# Controller_PCB.net
KiCad netlist of a schematic drawn in EasyEDA Pro
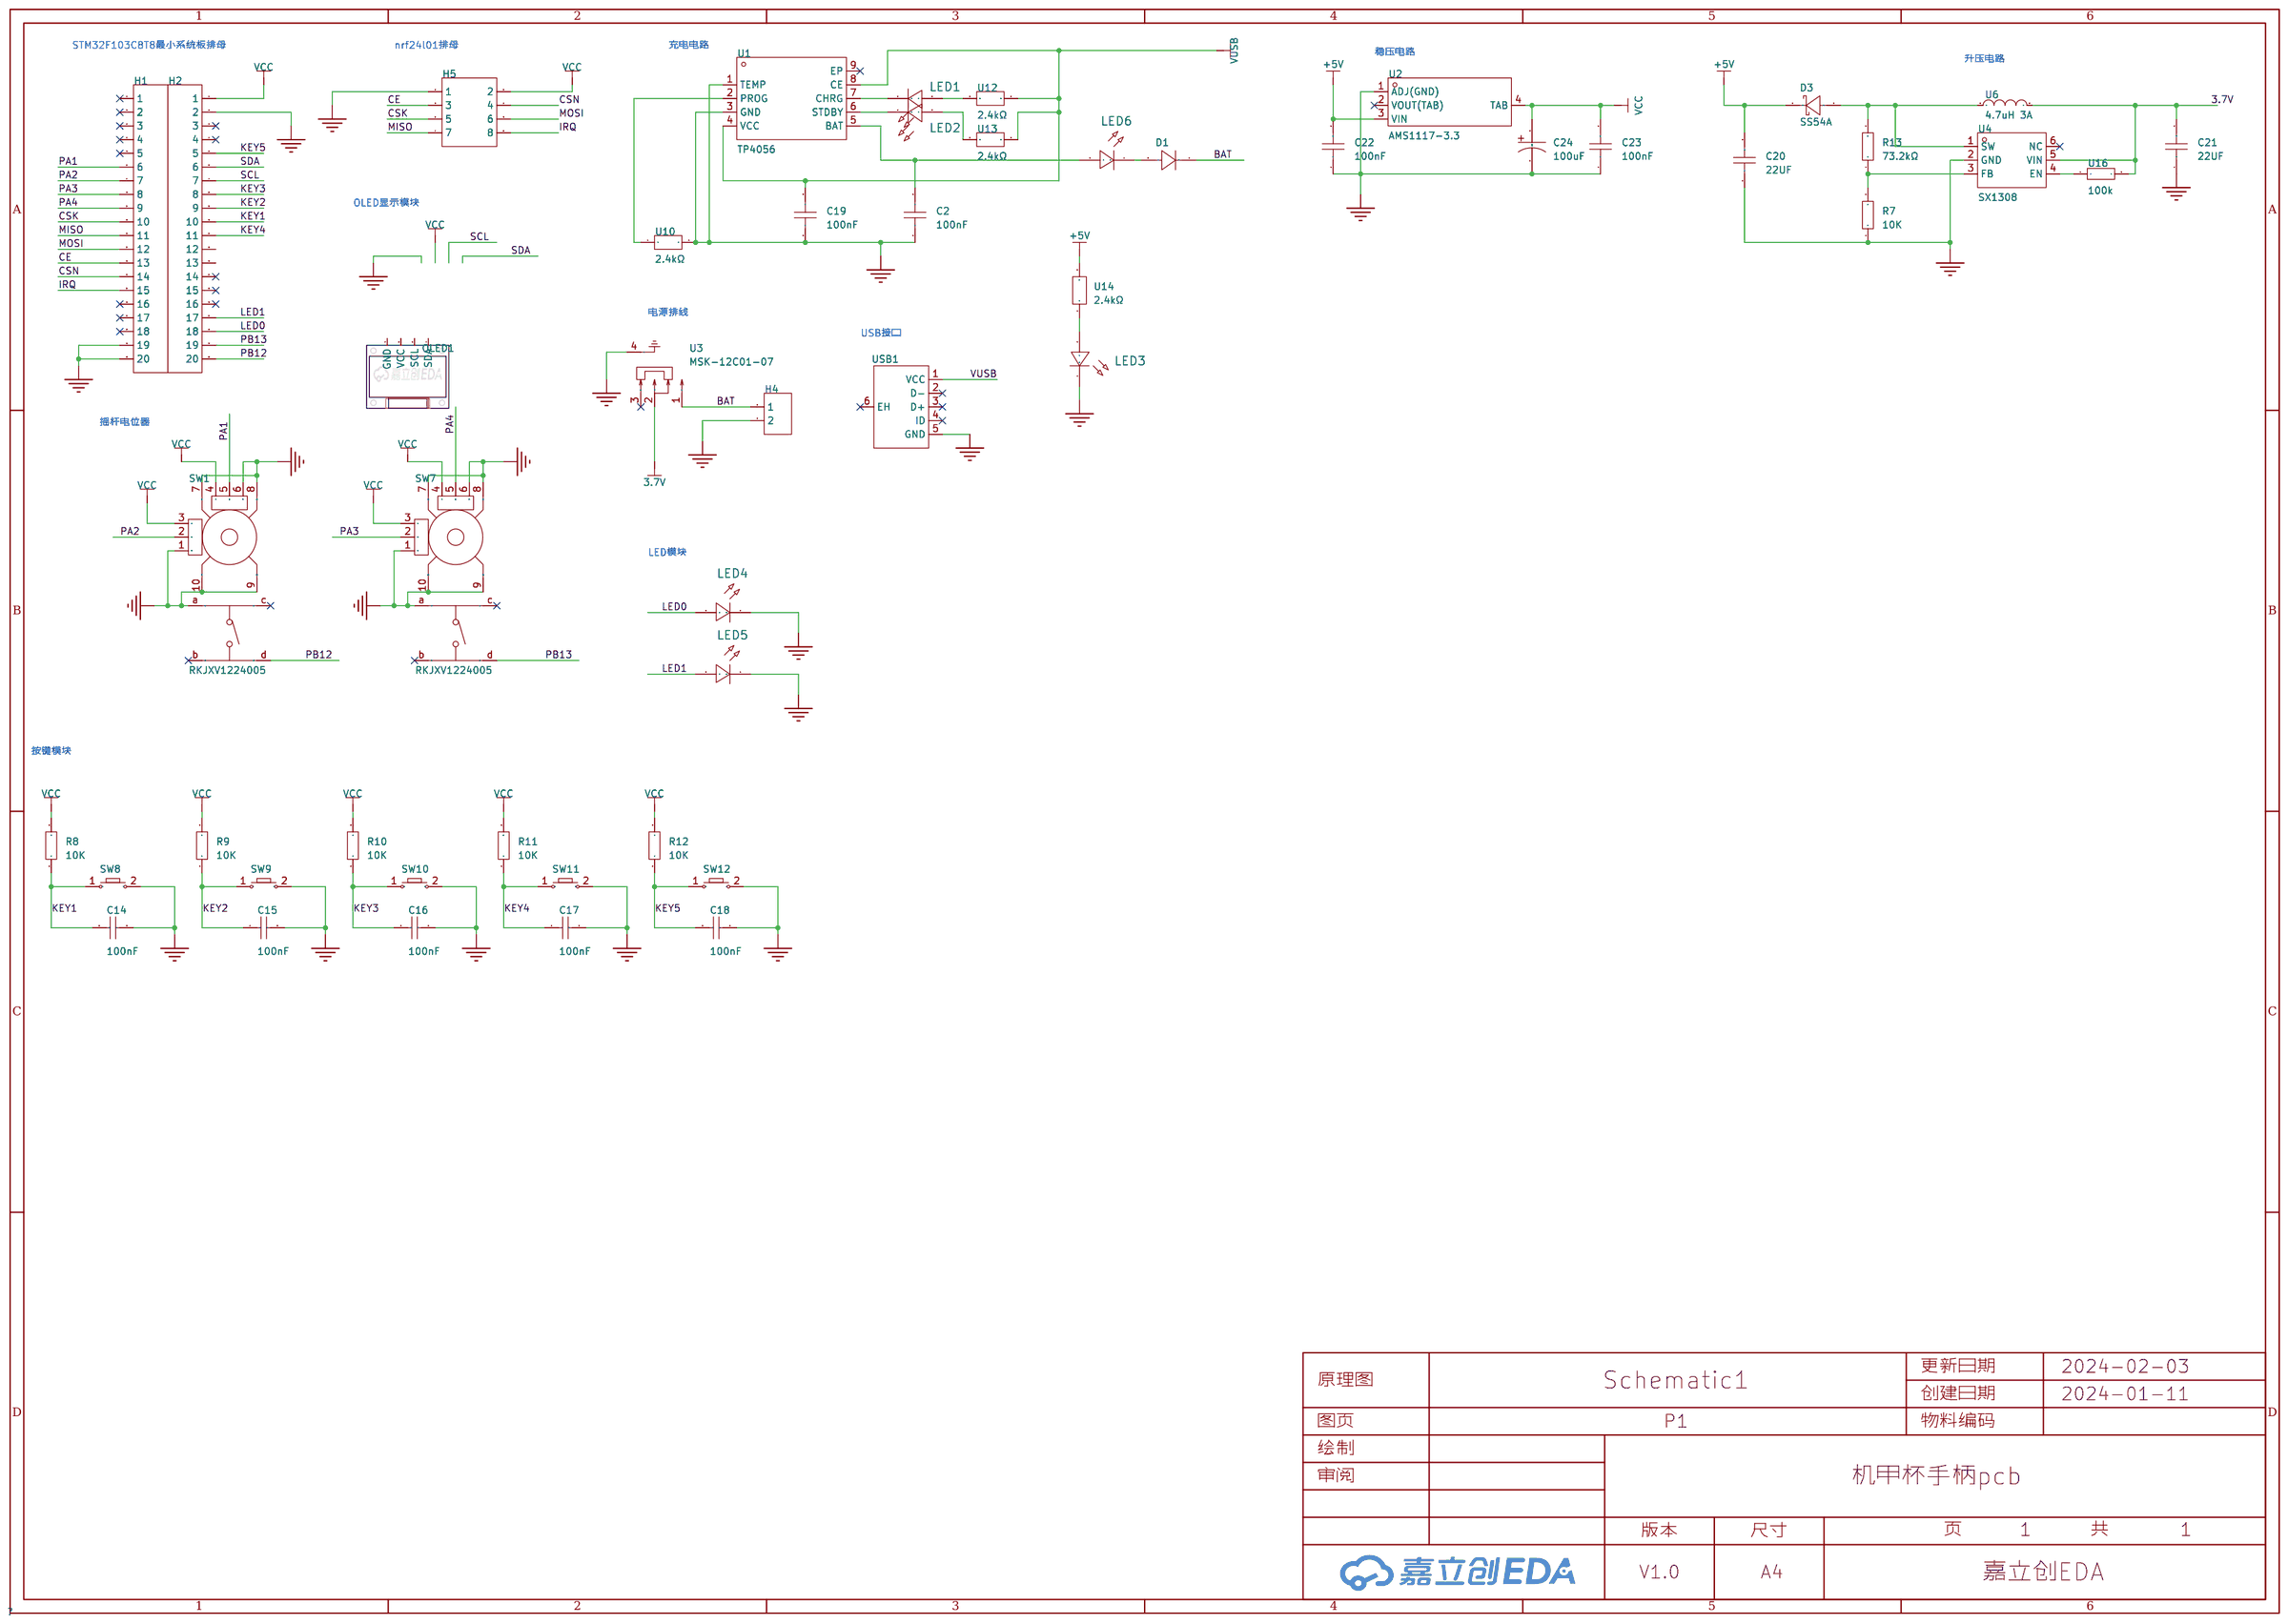
[diagram p0: schematic sheet]

(export (version "E")
  (design (tool "Eeschema 10.0.6"))
  (components
    (comp (ref "C2")
      (value "100nF")
      (footprint "easyedapro:C0805")
      (fields
        (field (name "Manufacturer Part") "CL21B104KCFNNNE")
        (field (name "Manufacturer") "SAMSUNG(三星)")
      )
      (libsource (lib "easyedapro") (part "CapAcitance"))
    )
    (comp (ref "C14")
      (value "100nF")
      (footprint "easyedapro:C0805")
      (description "容值:100nF;精度:±10%;额定电压:100V;材质(温度系数):X7R;")
      (fields
        (field (name "Manufacturer Part") "CL21B104KCFNNNE")
        (field (name "Manufacturer") "SAMSUNG(三星)")
      )
      (libsource (lib "easyedapro") (part "CL21B104KCFNNNE"))
    )
    (comp (ref "C15")
      (value "100nF")
      (footprint "easyedapro:C0805")
      (description "容值:100nF;精度:±10%;额定电压:100V;材质(温度系数):X7R;")
      (fields
        (field (name "Manufacturer Part") "CL21B104KCFNNNE")
        (field (name "Manufacturer") "SAMSUNG(三星)")
      )
      (libsource (lib "easyedapro") (part "CL21B104KCFNNNE"))
    )
    (comp (ref "C16")
      (value "100nF")
      (footprint "easyedapro:C0805")
      (description "容值:100nF;精度:±10%;额定电压:100V;材质(温度系数):X7R;")
      (fields
        (field (name "Manufacturer Part") "CL21B104KCFNNNE")
        (field (name "Manufacturer") "SAMSUNG(三星)")
      )
      (libsource (lib "easyedapro") (part "CL21B104KCFNNNE"))
    )
    (comp (ref "C17")
      (value "100nF")
      (footprint "easyedapro:C0805")
      (description "容值:100nF;精度:±10%;额定电压:100V;材质(温度系数):X7R;")
      (fields
        (field (name "Manufacturer Part") "CL21B104KCFNNNE")
        (field (name "Manufacturer") "SAMSUNG(三星)")
      )
      (libsource (lib "easyedapro") (part "CL21B104KCFNNNE"))
    )
    (comp (ref "C18")
      (value "100nF")
      (footprint "easyedapro:C0805")
      (description "容值:100nF;精度:±10%;额定电压:100V;材质(温度系数):X7R;")
      (fields
        (field (name "Manufacturer Part") "CL21B104KCFNNNE")
        (field (name "Manufacturer") "SAMSUNG(三星)")
      )
      (libsource (lib "easyedapro") (part "CL21B104KCFNNNE"))
    )
    (comp (ref "C19")
      (value "100nF")
      (footprint "easyedapro:C0805")
      (fields
        (field (name "Manufacturer Part") "CL21B104KCFNNNE")
        (field (name "Manufacturer") "SAMSUNG(三星)")
      )
      (libsource (lib "easyedapro") (part "CapAcitance"))
    )
    (comp (ref "C20")
      (value "22UF")
      (footprint "easyedapro:C1206")
      (libsource (lib "easyedapro") (part "22UF_C9900008064"))
    )
    (comp (ref "C21")
      (value "22UF")
      (footprint "easyedapro:C1206")
      (libsource (lib "easyedapro") (part "22UF_C9900008064"))
    )
    (comp (ref "C22")
      (value "100nF")
      (footprint "easyedapro:C0603")
      (description "容值:100nF;精度:±10%;额定电压:50V;材质(温度系数):X7R;")
      (fields
        (field (name "Manufacturer Part") "CC0603KRX7R9BB104")
        (field (name "Manufacturer") "YAGEO(国巨)")
      )
      (libsource (lib "easyedapro") (part "CC0603KRX7R9BB104"))
    )
    (comp (ref "C23")
      (value "100nF")
      (footprint "easyedapro:C0603")
      (description "容值:100nF;精度:±10%;额定电压:50V;材质(温度系数):X7R;")
      (fields
        (field (name "Manufacturer Part") "CC0603KRX7R9BB104")
        (field (name "Manufacturer") "YAGEO(国巨)")
      )
      (libsource (lib "easyedapro") (part "CC0603KRX7R9BB104"))
    )
    (comp (ref "C24")
      (value "100uF")
      (footprint "easyedapro:CASE-D_7343")
      (description "容值:100uF;精度:±20%;额定电压:6.3V;等效串联电阻:400mΩ@100kHz;")
      (fields (field (name "Manufacturer Part") "NOJD107M006RWJ") (field (name "Manufacturer") "Kyocera AVX"))
      (libsource (lib "easyedapro") (part "NOJD107M006RWJ"))
    )
    (comp (ref "D1")
      (value "~")
      (footprint "easyedapro:DO_1N4007")
      (libsource (lib "easyedapro") (part "D_1N4007"))
    )
    (comp (ref "D3")
      (value "SS54A")
      (footprint "easyedapro:SMA_L4.2-W2.6-LS5.1-RD")
      (description "二极管配置:独立式;正向压降(Vf):550mV@5A;直流反向耐压(Vr):40V;平均整流电流(Io):5A;")
      (fields (field (name "Manufacturer") "FUXINSEMI(富芯森美)"))
      (libsource (lib "easyedapro") (part "SS54A"))
    )
    (comp (ref "H1")
      (value "~")
      (footprint "easyedapro:HDR-TH_20P-P2.54-V-F")
      (libsource (lib "easyedapro") (part "HDR-F_2.54_1x20P"))
    )
    (comp (ref "H2")
      (value "~")
      (footprint "easyedapro:HDR-TH_20P-P2.54-V-F")
      (libsource (lib "easyedapro") (part "HDR-F_2.54_1x20P"))
    )
    (comp (ref "H4")
      (value "~")
      (footprint "easyedapro:HDR-TH_2P-P2.54-V-F")
      (libsource (lib "easyedapro") (part "Header-Female-2.54_1x2"))
    )
    (comp (ref "H5")
      (value "~")
      (footprint "easyedapro:HDR-TH_8P-P2.54-V-F-R2-C4-S2.54-1")
      (libsource (lib "easyedapro") (part "HDR-F-2.54_2x4"))
    )
    (comp (ref "LED1")
      (value "~")
      (footprint "easyedapro:LED_0603")
      (libsource (lib "easyedapro") (part "LED_R"))
    )
    (comp (ref "LED2")
      (value "~")
      (footprint "easyedapro:LED_0603")
      (libsource (lib "easyedapro") (part "LED_R"))
    )
    (comp (ref "LED3")
      (value "~")
      (footprint "easyedapro:LED_0603")
      (libsource (lib "easyedapro") (part "LED_R"))
    )
    (comp (ref "LED4")
      (value "~")
      (footprint "easyedapro:LED_0603")
      (libsource (lib "easyedapro") (part "LED_R"))
    )
    (comp (ref "LED5")
      (value "~")
      (footprint "easyedapro:LED_0603")
      (libsource (lib "easyedapro") (part "LED_R"))
    )
    (comp (ref "LED6")
      (value "~")
      (footprint "easyedapro:LED_0603")
      (libsource (lib "easyedapro") (part "LED_R"))
    )
    (comp (ref "OLED1")
      (value "~")
      (footprint "easyedapro:0.96OLED_4P")
      (libsource (lib "easyedapro") (part "0.96OLED模块_4P"))
    )
    (comp (ref "R7") (value "10K") (footprint "easyedapro:R1206") (libsource (lib "easyedapro") (part "电阻")))
    (comp (ref "R8") (value "10K") (footprint "easyedapro:R1206") (libsource (lib "easyedapro") (part "电阻")))
    (comp (ref "R9") (value "10K") (footprint "easyedapro:R1206") (libsource (lib "easyedapro") (part "电阻")))
    (comp (ref "R10") (value "10K") (footprint "easyedapro:R1206") (libsource (lib "easyedapro") (part "电阻")))
    (comp (ref "R11") (value "10K") (footprint "easyedapro:R1206") (libsource (lib "easyedapro") (part "电阻")))
    (comp (ref "R12") (value "10K") (footprint "easyedapro:R1206") (libsource (lib "easyedapro") (part "电阻")))
    (comp (ref "R13")
      (value "73.2kΩ")
      (footprint "easyedapro:R0603")
      (description "电阻类型:厚膜电阻;阻值:73.2kΩ;精度:±1%;功率:100mW;最大工作电压:75V;温度系数:±100ppm/°C;")
      (fields (field (name "Manufacturer Part") "AC0603FR-0773K2L") (field (name "Manufacturer") "YAGEO(国巨)"))
      (libsource (lib "easyedapro") (part "AC0603FR-0773K2L"))
    )
    (comp (ref "SW1")
      (value "RKJXV1224005")
      (footprint "easyedapro:SW-TH_RKJXV1224005")
      (description "操纵杆复位 中央按动开关 适用于航模玩具遥控器电位器、3D摇杆PS4手柄游戏机、无人机摇杆电位器、工业控制器")
      (fields (field (name "Manufacturer") "ALPSALPINE(阿尔卑斯阿尔派)"))
      (libsource (lib "easyedapro") (part "RKJXV1224005"))
    )
    (comp (ref "SW7")
      (value "RKJXV1224005")
      (footprint "easyedapro:SW-TH_RKJXV1224005")
      (description "操纵杆复位 中央按动开关 适用于航模玩具遥控器电位器、3D摇杆PS4手柄游戏机、无人机摇杆电位器、工业控制器")
      (fields (field (name "Manufacturer") "ALPSALPINE(阿尔卑斯阿尔派)"))
      (libsource (lib "easyedapro") (part "RKJXV1224005"))
    )
    (comp (ref "SW8")
      (value "~")
      (footprint "easyedapro:Key_SMD_3x4x2")
      (libsource (lib "easyedapro") (part "轻触按键x2"))
    )
    (comp (ref "SW9")
      (value "~")
      (footprint "easyedapro:Key_SMD_3x4x2")
      (libsource (lib "easyedapro") (part "轻触按键x2"))
    )
    (comp (ref "SW10")
      (value "~")
      (footprint "easyedapro:Key_SMD_3x4x2")
      (libsource (lib "easyedapro") (part "轻触按键x2"))
    )
    (comp (ref "SW11")
      (value "~")
      (footprint "easyedapro:Key_SMD_3x4x2")
      (libsource (lib "easyedapro") (part "轻触按键x2"))
    )
    (comp (ref "SW12")
      (value "~")
      (footprint "easyedapro:Key_SMD_3x4x2")
      (libsource (lib "easyedapro") (part "轻触按键x2"))
    )
    (comp (ref "U1")
      (value "TP4056")
      (footprint "easyedapro:ESOP-8_L4.9-W3.9-P1.27-LS6.0-BL-EP")
      (libsource (lib "easyedapro") (part "TP4056_C9900002169"))
    )
    (comp (ref "U2")
      (value "AMS1117-3.3")
      (footprint "easyedapro:SOT-223-4_L6.5-W3.5-P2.30-LS7.0-BR")
      (description "输出类型:固定;最大输入电压:18V;输出电压:3.3V;输出电流:1A;电源纹波抑制比(PSRR):60dB@(120Hz);输出极性:正;")
      (fields (field (name "Manufacturer") "UMW(友台半导体)"))
      (libsource (lib "easyedapro") (part "AMS1117-3.3_C347222"))
    )
    (comp (ref "U3")
      (value "MSK-12C01-07")
      (footprint "easyedapro:SW-SMD_MSK12CO2-BDM")
      (libsource (lib "easyedapro") (part "MSK-12C01-07"))
    )
    (comp (ref "U4")
      (value "SX1308")
      (footprint "easyedapro:SOT-23-6_L2.9-W1.6-P0.95-LS2.8-BL")
      (description "功能类型:升压型;同步整流:否;输出通道数:1;拓扑结构:升压式;输入电压:2V~24V;输出电压:28V;输出电流(最大值):-;开关频率:1.2MHz;")
      (fields (field (name "Manufacturer") "SX(硕芯科技)"))
      (libsource (lib "easyedapro") (part "SX1308"))
    )
    (comp (ref "U6")
      (value "4.7uH 3A")
      (footprint "easyedapro:IND-SMD_L7.3-W7.3_GSDRH74P")
      (libsource (lib "easyedapro") (part "4.7UH 3A"))
    )
    (comp (ref "U10")
      (value "2.4kΩ")
      (footprint "easyedapro:R0603")
      (description "电阻类型:薄膜电阻;阻值:2.4kΩ;精度:±0.1%;功率:100mW;最大工作电压:100V;温度系数:±10ppm/°C;")
      (fields (field (name "Manufacturer Part") "PTFR0603B2K40N9") (field (name "Manufacturer") "RESI(开步睿思）"))
      (libsource (lib "easyedapro") (part "PTFR0603B2K40N9"))
    )
    (comp (ref "U12")
      (value "2.4kΩ")
      (footprint "easyedapro:R0603")
      (description "电阻类型:薄膜电阻;阻值:2.4kΩ;精度:±0.1%;功率:100mW;最大工作电压:100V;温度系数:±10ppm/°C;")
      (fields (field (name "Manufacturer Part") "PTFR0603B2K40N9") (field (name "Manufacturer") "RESI(开步睿思）"))
      (libsource (lib "easyedapro") (part "PTFR0603B2K40N9"))
    )
    (comp (ref "U13")
      (value "2.4kΩ")
      (footprint "easyedapro:R0603")
      (description "电阻类型:薄膜电阻;阻值:2.4kΩ;精度:±0.1%;功率:100mW;最大工作电压:100V;温度系数:±10ppm/°C;")
      (fields (field (name "Manufacturer Part") "PTFR0603B2K40N9") (field (name "Manufacturer") "RESI(开步睿思）"))
      (libsource (lib "easyedapro") (part "PTFR0603B2K40N9"))
    )
    (comp (ref "U14")
      (value "2.4kΩ")
      (footprint "easyedapro:R0603")
      (description "电阻类型:薄膜电阻;阻值:2.4kΩ;精度:±0.1%;功率:100mW;最大工作电压:100V;温度系数:±10ppm/°C;")
      (fields (field (name "Manufacturer Part") "PTFR0603B2K40N9") (field (name "Manufacturer") "RESI(开步睿思）"))
      (libsource (lib "easyedapro") (part "PTFR0603B2K40N9"))
    )
    (comp (ref "U16")
      (value "100k")
      (footprint "easyedapro:R0603")
      (libsource (lib "easyedapro") (part "100K"))
    )
    (comp (ref "USB1")
      (value "~")
      (footprint "easyedapro:USB_Micro")
      (libsource (lib "easyedapro") (part "USB_Micro"))
    )
  )
  (nets
    (net (code "1") (name "+5V") (class "Default")
      (node (ref "C20") (pin "2") (pinfunction "2_2") (pintype "input"))
      (node (ref "C22") (pin "2") (pinfunction "2_2") (pintype "unspecified"))
      (node (ref "D3") (pin "1") (pinfunction "C_1") (pintype "unspecified"))
      (node (ref "U14") (pin "2") (pinfunction "2_2") (pintype "unspecified"))
      (node (ref "U2") (pin "3") (pinfunction "VIN_3") (pintype "unspecified"))
    )
    (net (code "2") (name "/BAT") (class "Default")
      (node (ref "D1") (pin "1") (pinfunction "K_1") (pintype "input"))
      (node (ref "H4") (pin "1") (pinfunction "1_1") (pintype "input"))
      (node (ref "U3") (pin "1") (pinfunction "1_1") (pintype "input"))
    )
    (net (code "3") (name "/CE") (class "Default")
      (node (ref "H1") (pin "13") (pinfunction "13_13") (pintype "input"))
      (node (ref "H5") (pin "3") (pinfunction "3_3") (pintype "input"))
    )
    (net (code "4") (name "/CSK") (class "Default")
      (node (ref "H1") (pin "10") (pinfunction "10_10") (pintype "input"))
      (node (ref "H5") (pin "5") (pinfunction "5_5") (pintype "input"))
    )
    (net (code "5") (name "/CSN") (class "Default")
      (node (ref "H1") (pin "14") (pinfunction "14_14") (pintype "input"))
      (node (ref "H5") (pin "4") (pinfunction "4_4") (pintype "input"))
    )
    (net (code "6") (name "/IRQ") (class "Default")
      (node (ref "H1") (pin "15") (pinfunction "15_15") (pintype "input"))
      (node (ref "H5") (pin "8") (pinfunction "8_8") (pintype "input"))
    )
    (net (code "7") (name "/KEY1") (class "Default")
      (node (ref "C14") (pin "1") (pinfunction "1_1") (pintype "input"))
      (node (ref "H2") (pin "10") (pinfunction "10_10") (pintype "input"))
      (node (ref "R8") (pin "1") (pinfunction "1_1") (pintype "input"))
      (node (ref "SW8") (pin "1") (pinfunction "1_1") (pintype "input"))
    )
    (net (code "8") (name "/KEY2") (class "Default")
      (node (ref "C15") (pin "1") (pinfunction "1_1") (pintype "input"))
      (node (ref "H2") (pin "9") (pinfunction "9_9") (pintype "input"))
      (node (ref "R9") (pin "1") (pinfunction "1_1") (pintype "input"))
      (node (ref "SW9") (pin "1") (pinfunction "1_1") (pintype "input"))
    )
    (net (code "9") (name "/KEY3") (class "Default")
      (node (ref "C16") (pin "1") (pinfunction "1_1") (pintype "input"))
      (node (ref "H2") (pin "8") (pinfunction "8_8") (pintype "input"))
      (node (ref "R10") (pin "1") (pinfunction "1_1") (pintype "input"))
      (node (ref "SW10") (pin "1") (pinfunction "1_1") (pintype "input"))
    )
    (net (code "10") (name "/KEY4") (class "Default")
      (node (ref "C17") (pin "1") (pinfunction "1_1") (pintype "input"))
      (node (ref "H2") (pin "11") (pinfunction "11_11") (pintype "input"))
      (node (ref "R11") (pin "1") (pinfunction "1_1") (pintype "input"))
      (node (ref "SW11") (pin "1") (pinfunction "1_1") (pintype "input"))
    )
    (net (code "11") (name "/KEY5") (class "Default")
      (node (ref "C18") (pin "1") (pinfunction "1_1") (pintype "input"))
      (node (ref "H2") (pin "5") (pinfunction "5_5") (pintype "input"))
      (node (ref "R12") (pin "1") (pinfunction "1_1") (pintype "input"))
      (node (ref "SW12") (pin "1") (pinfunction "1_1") (pintype "input"))
    )
    (net (code "12") (name "/LED0") (class "Default")
      (node (ref "H2") (pin "18") (pinfunction "18_18") (pintype "input"))
      (node (ref "LED4") (pin "2") (pinfunction "A_2") (pintype "input"))
    )
    (net (code "13") (name "/LED1") (class "Default")
      (node (ref "H2") (pin "17") (pinfunction "17_17") (pintype "input"))
      (node (ref "LED5") (pin "2") (pinfunction "A_2") (pintype "input"))
    )
    (net (code "14") (name "/MISO") (class "Default")
      (node (ref "H1") (pin "11") (pinfunction "11_11") (pintype "input"))
      (node (ref "H5") (pin "7") (pinfunction "7_7") (pintype "input"))
    )
    (net (code "15") (name "/MOSI") (class "Default")
      (node (ref "H1") (pin "12") (pinfunction "12_12") (pintype "input"))
      (node (ref "H5") (pin "6") (pinfunction "6_6") (pintype "input"))
    )
    (net (code "16") (name "/PA1") (class "Default")
      (node (ref "H1") (pin "6") (pinfunction "6_6") (pintype "input"))
      (node (ref "SW1") (pin "5") (pinfunction "DTA_5") (pintype "unspecified"))
    )
    (net (code "17") (name "/PA2") (class "Default")
      (node (ref "H1") (pin "7") (pinfunction "7_7") (pintype "input"))
      (node (ref "SW1") (pin "2") (pinfunction "DTA_2") (pintype "unspecified"))
    )
    (net (code "18") (name "/PA3") (class "Default")
      (node (ref "H1") (pin "8") (pinfunction "8_8") (pintype "input"))
      (node (ref "SW7") (pin "2") (pinfunction "DTA_2") (pintype "unspecified"))
    )
    (net (code "19") (name "/PA4") (class "Default")
      (node (ref "H1") (pin "9") (pinfunction "9_9") (pintype "input"))
      (node (ref "SW7") (pin "5") (pinfunction "DTA_5") (pintype "unspecified"))
    )
    (net (code "20") (name "/PB12") (class "Default")
      (node (ref "H2") (pin "20") (pinfunction "20_20") (pintype "input"))
      (node (ref "SW1") (pin "d") (pinfunction "d_d") (pintype "unspecified"))
    )
    (net (code "21") (name "/PB13") (class "Default")
      (node (ref "H2") (pin "19") (pinfunction "19_19") (pintype "input"))
      (node (ref "SW7") (pin "d") (pinfunction "d_d") (pintype "unspecified"))
    )
    (net (code "22") (name "/SCL") (class "Default")
      (node (ref "H2") (pin "7") (pinfunction "7_7") (pintype "input"))
    )
    (net (code "23") (name "/SDA") (class "Default")
      (node (ref "H2") (pin "6") (pinfunction "6_6") (pintype "input"))
    )
    (net (code "24") (name "3.7V") (class "Default")
      (node (ref "C21") (pin "2") (pinfunction "2_2") (pintype "input"))
      (node (ref "U16") (pin "2") (pinfunction "2_2") (pintype "input"))
      (node (ref "U3") (pin "2") (pinfunction "2_2") (pintype "input"))
      (node (ref "U4") (pin "5") (pinfunction "VIN_5") (pintype "input"))
      (node (ref "U6") (pin "2") (pinfunction "2_2") (pintype "input"))
    )
    (net (code "25") (name "GND") (class "Default")
      (node (ref "C14") (pin "2") (pinfunction "2_2") (pintype "input"))
      (node (ref "C15") (pin "2") (pinfunction "2_2") (pintype "input"))
      (node (ref "C16") (pin "2") (pinfunction "2_2") (pintype "input"))
      (node (ref "C17") (pin "2") (pinfunction "2_2") (pintype "input"))
      (node (ref "C18") (pin "2") (pinfunction "2_2") (pintype "input"))
      (node (ref "C19") (pin "1") (pinfunction "1_1") (pintype "input"))
      (node (ref "C2") (pin "1") (pinfunction "1_1") (pintype "input"))
      (node (ref "C20") (pin "1") (pinfunction "1_1") (pintype "input"))
      (node (ref "C21") (pin "1") (pinfunction "1_1") (pintype "input"))
      (node (ref "C22") (pin "1") (pinfunction "1_1") (pintype "unspecified"))
      (node (ref "C23") (pin "1") (pinfunction "1_1") (pintype "unspecified"))
      (node (ref "C24") (pin "2") (pinfunction "2_2") (pintype "input"))
      (node (ref "H1") (pin "19") (pinfunction "19_19") (pintype "input"))
      (node (ref "H1") (pin "20") (pinfunction "20_20") (pintype "input"))
      (node (ref "H2") (pin "2") (pinfunction "2_2") (pintype "input"))
      (node (ref "H4") (pin "2") (pinfunction "2_2") (pintype "input"))
      (node (ref "H5") (pin "1") (pinfunction "1_1") (pintype "input"))
      (node (ref "LED3") (pin "1") (pinfunction "C_1") (pintype "input"))
      (node (ref "LED4") (pin "1") (pinfunction "C_1") (pintype "input"))
      (node (ref "LED5") (pin "1") (pinfunction "C_1") (pintype "input"))
      (node (ref "R7") (pin "1") (pinfunction "1_1") (pintype "input"))
      (node (ref "SW1") (pin "1") (pinfunction "B_1") (pintype "unspecified"))
      (node (ref "SW1") (pin "10") (pinfunction "GND_10") (pintype "unspecified"))
      (node (ref "SW1") (pin "6") (pinfunction "B_6") (pintype "unspecified"))
      (node (ref "SW1") (pin "7") (pinfunction "GND_7") (pintype "unspecified"))
      (node (ref "SW1") (pin "8") (pinfunction "GND_8") (pintype "unspecified"))
      (node (ref "SW1") (pin "9") (pinfunction "GND_9") (pintype "unspecified"))
      (node (ref "SW1") (pin "a") (pinfunction "a_a") (pintype "unspecified"))
      (node (ref "SW10") (pin "2") (pinfunction "2_2") (pintype "input"))
      (node (ref "SW11") (pin "2") (pinfunction "2_2") (pintype "input"))
      (node (ref "SW12") (pin "2") (pinfunction "2_2") (pintype "input"))
      (node (ref "SW7") (pin "1") (pinfunction "B_1") (pintype "unspecified"))
      (node (ref "SW7") (pin "10") (pinfunction "GND_10") (pintype "unspecified"))
      (node (ref "SW7") (pin "6") (pinfunction "B_6") (pintype "unspecified"))
      (node (ref "SW7") (pin "7") (pinfunction "GND_7") (pintype "unspecified"))
      (node (ref "SW7") (pin "8") (pinfunction "GND_8") (pintype "unspecified"))
      (node (ref "SW7") (pin "9") (pinfunction "GND_9") (pintype "unspecified"))
      (node (ref "SW7") (pin "a") (pinfunction "a_a") (pintype "unspecified"))
      (node (ref "SW8") (pin "2") (pinfunction "2_2") (pintype "input"))
      (node (ref "SW9") (pin "2") (pinfunction "2_2") (pintype "input"))
      (node (ref "U1") (pin "1") (pinfunction "TEMP_1") (pintype "input"))
      (node (ref "U1") (pin "3") (pinfunction "GND_3") (pintype "input"))
      (node (ref "U10") (pin "2") (pinfunction "2_2") (pintype "unspecified"))
      (node (ref "U2") (pin "1") (pinfunction "ADJ(GND)_1") (pintype "unspecified"))
      (node (ref "U3") (pin "4") (pinfunction "4_4") (pintype "input"))
      (node (ref "U4") (pin "2") (pinfunction "GND_2") (pintype "input"))
      (node (ref "USB1") (pin "5") (pinfunction "GND_5") (pintype "input"))
    )
    (net (code "26") (name "Net-(D1-A)") (class "Default")
      (node (ref "D1") (pin "2") (pinfunction "A_2") (pintype "input"))
      (node (ref "LED6") (pin "1") (pinfunction "C_1") (pintype "input"))
    )
    (net (code "27") (name "Net-(D3-A)") (class "Default")
      (node (ref "D3") (pin "2") (pinfunction "A_2") (pintype "unspecified"))
      (node (ref "R13") (pin "2") (pinfunction "2_2") (pintype "unspecified"))
      (node (ref "U4") (pin "1") (pinfunction "SW_1") (pintype "input"))
      (node (ref "U6") (pin "1") (pinfunction "1_1") (pintype "input"))
    )
    (net (code "28") (name "Net-(LED1-A)") (class "Default")
      (node (ref "LED1") (pin "2") (pinfunction "A_2") (pintype "input"))
      (node (ref "U12") (pin "1") (pinfunction "1_1") (pintype "unspecified"))
    )
    (net (code "29") (name "Net-(LED1-C)") (class "Default")
      (node (ref "LED1") (pin "1") (pinfunction "C_1") (pintype "input"))
      (node (ref "U1") (pin "7") (pinfunction "CHRG_7") (pintype "input"))
    )
    (net (code "30") (name "Net-(LED2-A)") (class "Default")
      (node (ref "LED2") (pin "2") (pinfunction "A_2") (pintype "input"))
      (node (ref "U13") (pin "1") (pinfunction "1_1") (pintype "unspecified"))
    )
    (net (code "31") (name "Net-(LED2-C)") (class "Default")
      (node (ref "LED2") (pin "1") (pinfunction "C_1") (pintype "input"))
      (node (ref "U1") (pin "6") (pinfunction "STDBY_6") (pintype "input"))
    )
    (net (code "32") (name "Net-(LED3-A)") (class "Default")
      (node (ref "LED3") (pin "2") (pinfunction "A_2") (pintype "input"))
      (node (ref "U14") (pin "1") (pinfunction "1_1") (pintype "unspecified"))
    )
    (net (code "33") (name "Net-(LED6-A)") (class "Default")
      (node (ref "C2") (pin "2") (pinfunction "2_2") (pintype "input"))
      (node (ref "LED6") (pin "2") (pinfunction "A_2") (pintype "input"))
      (node (ref "U1") (pin "5") (pinfunction "BAT_5") (pintype "input"))
    )
    (net (code "34") (name "Net-(U1-PROG)") (class "Default")
      (node (ref "U1") (pin "2") (pinfunction "PROG_2") (pintype "input"))
      (node (ref "U10") (pin "1") (pinfunction "1_1") (pintype "unspecified"))
    )
    (net (code "35") (name "Net-(U4-EN)") (class "Default")
      (node (ref "U16") (pin "1") (pinfunction "1_1") (pintype "input"))
      (node (ref "U4") (pin "4") (pinfunction "EN_4") (pintype "input"))
    )
    (net (code "36") (name "Net-(U4-FB)") (class "Default")
      (node (ref "R13") (pin "1") (pinfunction "1_1") (pintype "unspecified"))
      (node (ref "R7") (pin "2") (pinfunction "2_2") (pintype "input"))
      (node (ref "U4") (pin "3") (pinfunction "FB_3") (pintype "input"))
    )
    (net (code "37") (name "VCC") (class "Default")
      (node (ref "C23") (pin "2") (pinfunction "2_2") (pintype "unspecified"))
      (node (ref "C24") (pin "1") (pinfunction "1_1") (pintype "input"))
      (node (ref "H2") (pin "1") (pinfunction "1_1") (pintype "input"))
      (node (ref "H5") (pin "2") (pinfunction "2_2") (pintype "input"))
      (node (ref "R10") (pin "2") (pinfunction "2_2") (pintype "input"))
      (node (ref "R11") (pin "2") (pinfunction "2_2") (pintype "input"))
      (node (ref "R12") (pin "2") (pinfunction "2_2") (pintype "input"))
      (node (ref "R8") (pin "2") (pinfunction "2_2") (pintype "input"))
      (node (ref "R9") (pin "2") (pinfunction "2_2") (pintype "input"))
      (node (ref "SW1") (pin "3") (pinfunction "A_3") (pintype "unspecified"))
      (node (ref "SW1") (pin "4") (pinfunction "A_4") (pintype "unspecified"))
      (node (ref "SW7") (pin "3") (pinfunction "A_3") (pintype "unspecified"))
      (node (ref "SW7") (pin "4") (pinfunction "A_4") (pintype "unspecified"))
      (node (ref "U2") (pin "4") (pinfunction "TAB_4") (pintype "unspecified"))
    )
    (net (code "38") (name "VUSB") (class "Default")
      (node (ref "C19") (pin "2") (pinfunction "2_2") (pintype "input"))
      (node (ref "U1") (pin "4") (pinfunction "VCC_4") (pintype "input"))
      (node (ref "U1") (pin "8") (pinfunction "CE_8") (pintype "input"))
      (node (ref "U12") (pin "2") (pinfunction "2_2") (pintype "unspecified"))
      (node (ref "U13") (pin "2") (pinfunction "2_2") (pintype "unspecified"))
      (node (ref "USB1") (pin "1") (pinfunction "VCC_1") (pintype "input"))
    )
    (net (code "39") (name "unconnected-(H1-Pad1)") (class "Default")
      (node (ref "H1") (pin "1") (pinfunction "1_1") (pintype "input+no_connect"))
    )
    (net (code "40") (name "unconnected-(H1-Pad2)") (class "Default")
      (node (ref "H1") (pin "2") (pinfunction "2_2") (pintype "input+no_connect"))
    )
    (net (code "41") (name "unconnected-(H1-Pad3)") (class "Default")
      (node (ref "H1") (pin "3") (pinfunction "3_3") (pintype "input+no_connect"))
    )
    (net (code "42") (name "unconnected-(H1-Pad4)") (class "Default")
      (node (ref "H1") (pin "4") (pinfunction "4_4") (pintype "input+no_connect"))
    )
    (net (code "43") (name "unconnected-(H1-Pad5)") (class "Default")
      (node (ref "H1") (pin "5") (pinfunction "5_5") (pintype "input+no_connect"))
    )
    (net (code "44") (name "unconnected-(H1-Pad16)") (class "Default")
      (node (ref "H1") (pin "16") (pinfunction "16_16") (pintype "input+no_connect"))
    )
    (net (code "45") (name "unconnected-(H1-Pad17)") (class "Default")
      (node (ref "H1") (pin "17") (pinfunction "17_17") (pintype "input+no_connect"))
    )
    (net (code "46") (name "unconnected-(H1-Pad18)") (class "Default")
      (node (ref "H1") (pin "18") (pinfunction "18_18") (pintype "input+no_connect"))
    )
    (net (code "47") (name "unconnected-(H2-Pad3)") (class "Default")
      (node (ref "H2") (pin "3") (pinfunction "3_3") (pintype "input+no_connect"))
    )
    (net (code "48") (name "unconnected-(H2-Pad4)") (class "Default")
      (node (ref "H2") (pin "4") (pinfunction "4_4") (pintype "input+no_connect"))
    )
    (net (code "49") (name "unconnected-(H2-Pad12)") (class "Default")
      (node (ref "H2") (pin "12") (pinfunction "12_12") (pintype "input"))
    )
    (net (code "50") (name "unconnected-(H2-Pad13)") (class "Default")
      (node (ref "H2") (pin "13") (pinfunction "13_13") (pintype "input"))
    )
    (net (code "51") (name "unconnected-(H2-Pad14)") (class "Default")
      (node (ref "H2") (pin "14") (pinfunction "14_14") (pintype "input+no_connect"))
    )
    (net (code "52") (name "unconnected-(H2-Pad15)") (class "Default")
      (node (ref "H2") (pin "15") (pinfunction "15_15") (pintype "input+no_connect"))
    )
    (net (code "53") (name "unconnected-(H2-Pad16)") (class "Default")
      (node (ref "H2") (pin "16") (pinfunction "16_16") (pintype "input+no_connect"))
    )
    (net (code "54") (name "unconnected-(OLED1-GND-Pad1)") (class "Default")
      (node (ref "OLED1") (pin "1") (pinfunction "GND_1") (pintype "input"))
    )
    (net (code "55") (name "unconnected-(OLED1-SCL-Pad3)") (class "Default")
      (node (ref "OLED1") (pin "3") (pinfunction "SCL_3") (pintype "input"))
    )
    (net (code "56") (name "unconnected-(OLED1-SDA-Pad4)") (class "Default")
      (node (ref "OLED1") (pin "4") (pinfunction "SDA_4") (pintype "input"))
    )
    (net (code "57") (name "unconnected-(OLED1-VCC-Pad2)") (class "Default")
      (node (ref "OLED1") (pin "2") (pinfunction "VCC_2") (pintype "input"))
    )
    (net (code "58") (name "unconnected-(SW1-Padb)") (class "Default")
      (node (ref "SW1") (pin "b") (pinfunction "b_b") (pintype "unspecified+no_connect"))
    )
    (net (code "59") (name "unconnected-(SW1-Padc)") (class "Default")
      (node (ref "SW1") (pin "c") (pinfunction "c_c") (pintype "unspecified+no_connect"))
    )
    (net (code "60") (name "unconnected-(SW7-Padb)") (class "Default")
      (node (ref "SW7") (pin "b") (pinfunction "b_b") (pintype "unspecified+no_connect"))
    )
    (net (code "61") (name "unconnected-(SW7-Padc)") (class "Default")
      (node (ref "SW7") (pin "c") (pinfunction "c_c") (pintype "unspecified+no_connect"))
    )
    (net (code "62") (name "unconnected-(U1-EP-Pad9)") (class "Default")
      (node (ref "U1") (pin "9") (pinfunction "EP_9") (pintype "input+no_connect"))
    )
    (net (code "63") (name "unconnected-(U2-VOUT(TAB)-Pad2)") (class "Default")
      (node (ref "U2") (pin "2") (pinfunction "VOUT(TAB)_2") (pintype "unspecified+no_connect"))
    )
    (net (code "64") (name "unconnected-(U3-Pad3)") (class "Default")
      (node (ref "U3") (pin "3") (pinfunction "3_3") (pintype "input+no_connect"))
    )
    (net (code "65") (name "unconnected-(U4-NC-Pad6)") (class "Default")
      (node (ref "U4") (pin "6") (pinfunction "NC_6") (pintype "input+no_connect"))
    )
    (net (code "66") (name "unconnected-(USB1-D+-Pad3)") (class "Default")
      (node (ref "USB1") (pin "3") (pinfunction "D+_3") (pintype "input+no_connect"))
    )
    (net (code "67") (name "unconnected-(USB1-D--Pad2)") (class "Default")
      (node (ref "USB1") (pin "2") (pinfunction "D-_2") (pintype "input+no_connect"))
    )
    (net (code "68") (name "unconnected-(USB1-EH-Pad6)") (class "Default")
      (node (ref "USB1") (pin "6") (pinfunction "EH_6") (pintype "input+no_connect"))
    )
    (net (code "69") (name "unconnected-(USB1-ID-Pad4)") (class "Default")
      (node (ref "USB1") (pin "4") (pinfunction "ID_4") (pintype "input+no_connect"))
    )
  )
)
